# Encoder2.net
KiCad netlist of a schematic drawn in Altium Designer
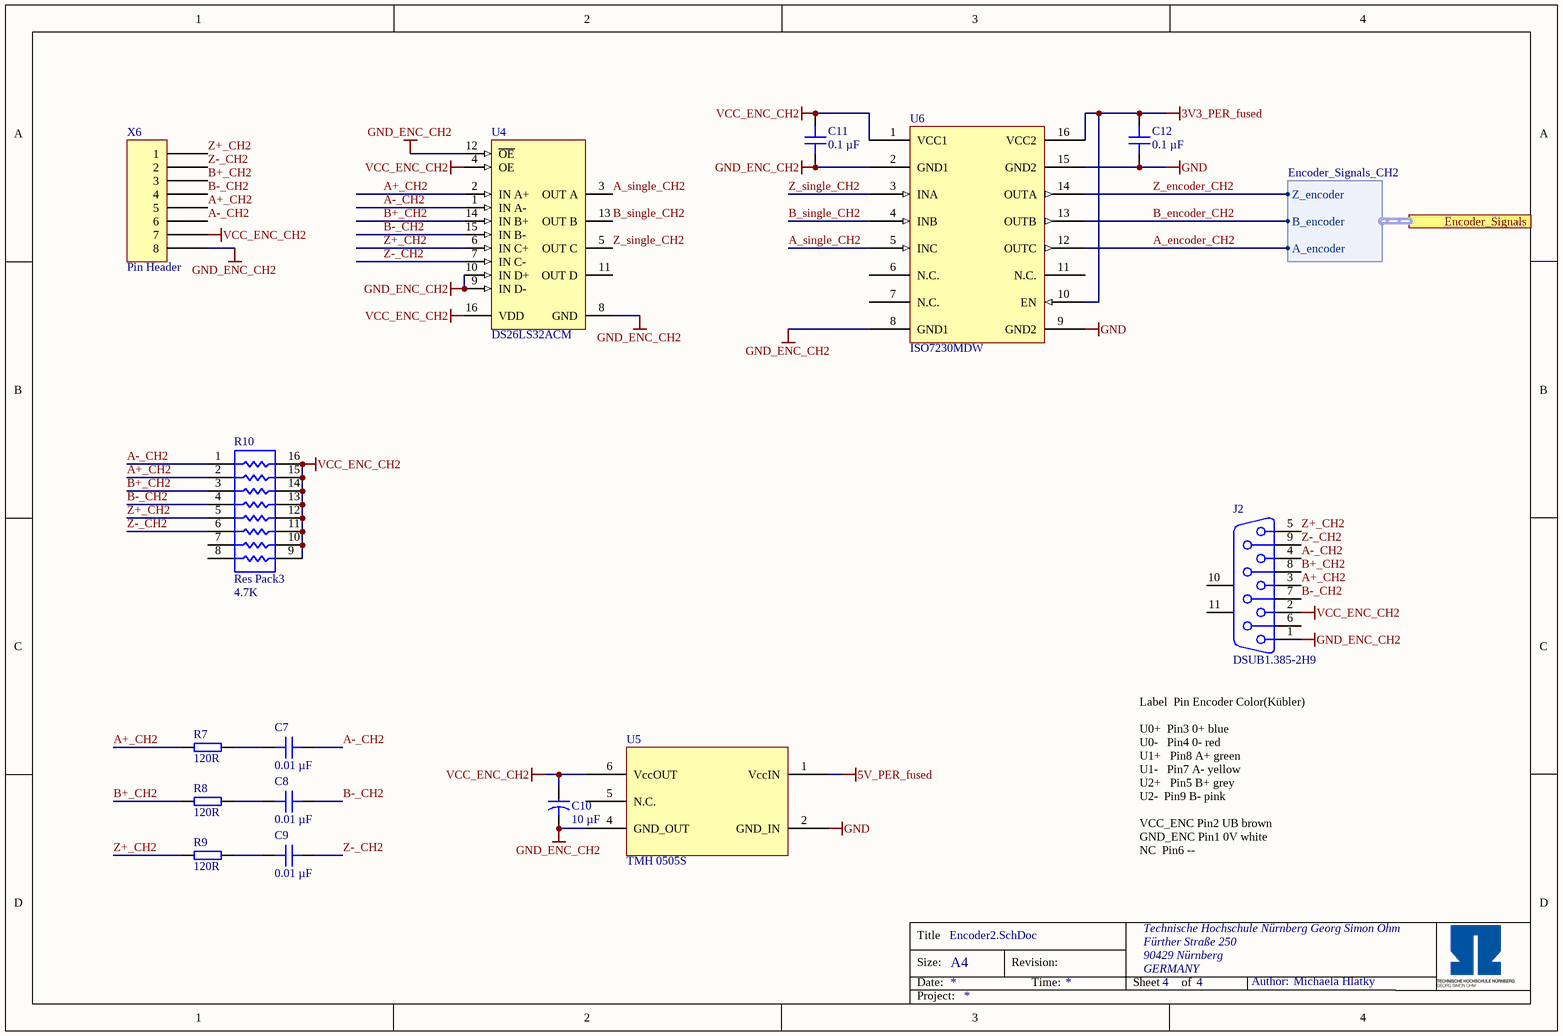
[diagram p0: Encoder2.SchDoc]

(export (version "E")
  (design (tool "Eeschema 10.0.6"))
  (components
    (comp (ref "C7")
      (value "0.01 µF")
      (footprint "C_0805")
      (description "Capacitor 0805, 100 VDC, 0.01 µF, X7R")
      (fields
        (field (name "MANUFACTURER PART NUMBER") "GRM21BR72A103KA01L")
        (field (name "MANUFACTURER") "Murata Electronics")
        (field (name "CREATED FROM") "MGremer")
      )
      (libsource (lib "user") (part "Capacitor"))
    )
    (comp (ref "C8")
      (value "0.01 µF")
      (footprint "C_0805")
      (description "Capacitor 0805, 100 VDC, 0.01 µF, X7R")
      (fields
        (field (name "MANUFACTURER PART NUMBER") "GRM21BR72A103KA01L")
        (field (name "MANUFACTURER") "Murata Electronics")
        (field (name "CREATED FROM") "MGremer")
      )
      (libsource (lib "user") (part "Capacitor"))
    )
    (comp (ref "C9")
      (value "0.01 µF")
      (footprint "C_0805")
      (description "Capacitor 0805, 100 VDC, 0.01 µF, X7R")
      (fields
        (field (name "MANUFACTURER PART NUMBER") "GRM21BR72A103KA01L")
        (field (name "MANUFACTURER") "Murata Electronics")
        (field (name "CREATED FROM") "MGremer")
      )
      (libsource (lib "user") (part "Capacitor"))
    )
    (comp (ref "C10")
      (value "10 µF")
      (footprint "CAPR5-4X5")
      (description "Capacitor; 2 Leads")
      (fields
        (field (name "MANUFACTURER PART NUMBER") "CAPR5-4X5")
        (field (name "PUBLISHER") "Altium Limited")
        (field (name "CREATED FROM") "MHlatky")
      )
      (libsource (lib "user") (part "Cap2"))
    )
    (comp (ref "C11")
      (value "0.1 µF")
      (footprint "C_0805")
      (description "Capacitor 0805, 50 VDC, 0.1 µF, X7R")
      (fields
        (field (name "MANUFACTURER PART NUMBER") "C0805C104J5RECTU")
        (field (name "MANUFACTURER") "KEMET")
        (field (name "CREATED FROM") "MGremer")
      )
      (libsource (lib "user") (part "Capacitor"))
    )
    (comp (ref "C12")
      (value "0.1 µF")
      (footprint "C_0805")
      (description "Capacitor 0805, 50 VDC, 0.1 µF, X7R")
      (fields
        (field (name "MANUFACTURER PART NUMBER") "C0805C104J5RECTU")
        (field (name "MANUFACTURER") "KEMET")
        (field (name "CREATED FROM") "MGremer")
      )
      (libsource (lib "user") (part "Capacitor"))
    )
    (comp (ref "J2")
      (value "DSUB1.385-2H9")
      (footprint "DSUB1.385-2H9")
      (description "Connector; D Subminiature; 9 Position; Right Angle; Pitch 1.385 mm")
      (fields
        (field (name "MANUFACTURER") "Altium")
        (field (name "PUBLISHER") "Altium Limited")
        (field (name "CREATED FROM") "MHlatky")
      )
      (libsource (lib "user") (part "D Connector 9"))
    )
    (comp (ref "R7")
      (value "120R")
      (footprint "RES 0603_1608")
      (description "SMD resistor E24 series")
      (fields
        (field (name "MANUFACTURER PART NUMBER") "RK73B1JTTD121J")
        (field (name "MANUFACTURER") "KOA Speer")
        (field (name "CREATED FROM") "MGremer")
      )
      (libsource (lib "user") (part "Resistor"))
    )
    (comp (ref "R8")
      (value "120R")
      (footprint "RES 0603_1608")
      (description "SMD resistor E24 series")
      (fields
        (field (name "MANUFACTURER PART NUMBER") "RK73B1JTTD121J")
        (field (name "MANUFACTURER") "KOA Speer")
        (field (name "CREATED FROM") "MGremer")
      )
      (libsource (lib "user") (part "Resistor"))
    )
    (comp (ref "R9")
      (value "120R")
      (footprint "RES 0603_1608")
      (description "SMD resistor E24 series")
      (fields
        (field (name "MANUFACTURER PART NUMBER") "RK73B1JTTD121J")
        (field (name "MANUFACTURER") "KOA Speer")
        (field (name "CREATED FROM") "MGremer")
      )
      (libsource (lib "user") (part "Resistor"))
    )
    (comp (ref "R10")
      (value "Res Pack3")
      (footprint "SO-16_N")
      (description "SOIC, 16-Leads, Body 9.9x3.9mm, Pitch 1.27mm, IPC Medium Density")
      (fields
        (field (name "ALTIUM_VALUE") "4.7K")
        (field (name "PUBLISHER") "Altium Limited")
        (field (name "CREATED FROM") "MHlatky")
      )
      (libsource (lib "user") (part "Res Pack3"))
    )
    (comp (ref "U4")
      (value "DS26LS32ACM")
      (footprint "M16A_M")
      (description "DS26LS32AC/DS26LS32C/DS26LS32M/DS26LS33M Quad Differential Line Receivers")
      (fields
        (field (name "MANUFACTURER") "Texas Instruments")
        (field (name "PUBLISHER") "Altium Limited")
        (field (name "CREATED FROM") "MHlatky")
      )
      (libsource (lib "user") (part "DS26LS32ACM"))
    )
    (comp (ref "U5")
      (value "TMH 0505S")
      (footprint "SIL-6(7)")
      (fields (field (name "MANUFACTURER") "Traco") (field (name "CREATED FROM") "MHlatky"))
      (libsource (lib "user") (part "TRACO TMH 0505S"))
    )
    (comp (ref "U6")
      (value "ISO7230MDW")
      (footprint "TI ISO7230 SOIC")
      (description "ISO723xx High-Speed, Triple-Channel Digital Isolators")
      (fields (field (name "MANUFACTURER") "Analog Devices") (field (name "CREATED FROM") "MHlatky"))
      (libsource (lib "user") (part "TI ISO7230"))
    )
    (comp (ref "X6")
      (value "Pin Header")
      (footprint "HDR1X8")
      (description "8 Pin")
      (fields (field (name "MANUFACTURER PART NUMBER") "HDR1X8") (field (name "CREATED FROM") "MHlatky"))
      (libsource (lib "user") (part "8 Pin"))
    )
  )
  (nets
    (net (code "2") (name "/A+_CH2") (class "Default")
      (node (ref "J2") (pin "3") (pinfunction "3_3") (pintype "passive"))
      (node (ref "R10") (pin "2") (pinfunction "2_2") (pintype "passive"))
      (node (ref "R7") (pin "1") (pinfunction "1_1") (pintype "passive"))
      (node (ref "U4") (pin "2") (pinfunction "IN_A+_2") (pintype "input"))
      (node (ref "X6") (pin "5") (pinfunction "5_5") (pintype "passive"))
    )
    (net (code "3") (name "/A-_CH2") (class "Default")
      (node (ref "C7") (pin "2") (pinfunction "2_2") (pintype "passive"))
      (node (ref "J2") (pin "4") (pinfunction "4_4") (pintype "passive"))
      (node (ref "R10") (pin "1") (pinfunction "1_1") (pintype "passive"))
      (node (ref "U4") (pin "1") (pinfunction "IN_A-_1") (pintype "input"))
      (node (ref "X6") (pin "6") (pinfunction "6_6") (pintype "passive"))
    )
    (net (code "4") (name "/A_encoder_CH2") (class "Default")
      (node (ref "U6") (pin "12") (pinfunction "OUTC_12") (pintype "output"))
    )
    (net (code "5") (name "/A_single_CH2") (class "Default")
      (node (ref "U4") (pin "3") (pinfunction "OUT_A_3") (pintype "tri_state"))
      (node (ref "U6") (pin "5") (pinfunction "INC_5") (pintype "input"))
    )
    (net (code "6") (name "/B+_CH2") (class "Default")
      (node (ref "J2") (pin "8") (pinfunction "8_8") (pintype "passive"))
      (node (ref "R10") (pin "3") (pinfunction "3_3") (pintype "passive"))
      (node (ref "R8") (pin "1") (pinfunction "1_1") (pintype "passive"))
      (node (ref "U4") (pin "14") (pinfunction "IN_B+_14") (pintype "input"))
      (node (ref "X6") (pin "3") (pinfunction "3_3") (pintype "passive"))
    )
    (net (code "7") (name "/B-_CH2") (class "Default")
      (node (ref "C8") (pin "2") (pinfunction "2_2") (pintype "passive"))
      (node (ref "J2") (pin "7") (pinfunction "7_7") (pintype "passive"))
      (node (ref "R10") (pin "4") (pinfunction "4_4") (pintype "passive"))
      (node (ref "U4") (pin "15") (pinfunction "IN_B-_15") (pintype "input"))
      (node (ref "X6") (pin "4") (pinfunction "4_4") (pintype "passive"))
    )
    (net (code "8") (name "/B_encoder_CH2") (class "Default")
      (node (ref "U6") (pin "13") (pinfunction "OUTB_13") (pintype "output"))
    )
    (net (code "9") (name "/B_single_CH2") (class "Default")
      (node (ref "U4") (pin "13") (pinfunction "OUT_B_13") (pintype "tri_state"))
      (node (ref "U6") (pin "4") (pinfunction "INB_4") (pintype "input"))
    )
    (net (code "10") (name "/Z+_CH2") (class "Default")
      (node (ref "J2") (pin "5") (pinfunction "5_5") (pintype "passive"))
      (node (ref "R10") (pin "5") (pinfunction "5_5") (pintype "passive"))
      (node (ref "R9") (pin "1") (pinfunction "1_1") (pintype "passive"))
      (node (ref "U4") (pin "6") (pinfunction "IN_C+_6") (pintype "input"))
      (node (ref "X6") (pin "1") (pinfunction "1_1") (pintype "passive"))
    )
    (net (code "11") (name "/Z-_CH2") (class "Default")
      (node (ref "C9") (pin "2") (pinfunction "2_2") (pintype "passive"))
      (node (ref "J2") (pin "9") (pinfunction "9_9") (pintype "passive"))
      (node (ref "R10") (pin "6") (pinfunction "6_6") (pintype "passive"))
      (node (ref "U4") (pin "7") (pinfunction "IN_C-_7") (pintype "input"))
      (node (ref "X6") (pin "2") (pinfunction "2_2") (pintype "passive"))
    )
    (net (code "12") (name "/Z_encoder_CH2") (class "Default")
      (node (ref "U6") (pin "14") (pinfunction "OUTA_14") (pintype "output"))
    )
    (net (code "13") (name "/Z_single_CH2") (class "Default")
      (node (ref "U4") (pin "5") (pinfunction "OUT_C_5") (pintype "tri_state"))
      (node (ref "U6") (pin "3") (pinfunction "INA_3") (pintype "input"))
    )
    (net (code "15") (name "3V3_PER_fused") (class "Default")
      (node (ref "C12") (pin "2") (pinfunction "2_2") (pintype "passive"))
      (node (ref "U6") (pin "10") (pinfunction "EN_10") (pintype "input"))
      (node (ref "U6") (pin "16") (pinfunction "VCC2_16") (pintype "passive"))
    )
    (net (code "16") (name "5V_PER_fused") (class "Default")
      (node (ref "U5") (pin "1") (pinfunction "VccIN_1") (pintype "passive"))
    )
    (net (code "17") (name "GND") (class "Default")
      (node (ref "C12") (pin "1") (pinfunction "1_1") (pintype "passive"))
      (node (ref "U5") (pin "2") (pinfunction "GND_IN_2") (pintype "passive"))
      (node (ref "U6") (pin "15") (pinfunction "GND2_15") (pintype "passive"))
      (node (ref "U6") (pin "9") (pinfunction "GND2_9") (pintype "passive"))
    )
    (net (code "18") (name "GND_ENC_CH2") (class "Default")
      (node (ref "C10") (pin "2") (pinfunction "2_2") (pintype "passive"))
      (node (ref "C11") (pin "1") (pinfunction "1_1") (pintype "passive"))
      (node (ref "J2") (pin "1") (pinfunction "1_1") (pintype "passive"))
      (node (ref "U4") (pin "10") (pinfunction "IN_D+_10") (pintype "input"))
      (node (ref "U4") (pin "12") (pinfunction "~{OE}_12") (pintype "input"))
      (node (ref "U4") (pin "8") (pinfunction "GND_8") (pintype "power_in"))
      (node (ref "U4") (pin "9") (pinfunction "IN_D-_9") (pintype "input"))
      (node (ref "U5") (pin "4") (pinfunction "GND_OUT_4") (pintype "passive"))
      (node (ref "U6") (pin "2") (pinfunction "GND1_2") (pintype "passive"))
      (node (ref "U6") (pin "8") (pinfunction "GND1_8") (pintype "passive"))
      (node (ref "X6") (pin "8") (pinfunction "8_8") (pintype "passive"))
    )
    (net (code "19") (name "Net-(C7-Pad1)") (class "Default")
      (node (ref "C7") (pin "1") (pinfunction "1_1") (pintype "passive"))
      (node (ref "R7") (pin "2") (pinfunction "2_2") (pintype "passive"))
    )
    (net (code "20") (name "Net-(C8-Pad1)") (class "Default")
      (node (ref "C8") (pin "1") (pinfunction "1_1") (pintype "passive"))
      (node (ref "R8") (pin "2") (pinfunction "2_2") (pintype "passive"))
    )
    (net (code "21") (name "Net-(C9-Pad1)") (class "Default")
      (node (ref "C9") (pin "1") (pinfunction "1_1") (pintype "passive"))
      (node (ref "R9") (pin "2") (pinfunction "2_2") (pintype "passive"))
    )
    (net (code "22") (name "VCC_ENC_CH2") (class "Default")
      (node (ref "C10") (pin "1") (pinfunction "1_1") (pintype "passive"))
      (node (ref "C11") (pin "2") (pinfunction "2_2") (pintype "passive"))
      (node (ref "J2") (pin "2") (pinfunction "2_2") (pintype "passive"))
      (node (ref "R10") (pin "10") (pinfunction "10_10") (pintype "passive"))
      (node (ref "R10") (pin "11") (pinfunction "11_11") (pintype "passive"))
      (node (ref "R10") (pin "12") (pinfunction "12_12") (pintype "passive"))
      (node (ref "R10") (pin "13") (pinfunction "13_13") (pintype "passive"))
      (node (ref "R10") (pin "14") (pinfunction "14_14") (pintype "passive"))
      (node (ref "R10") (pin "15") (pinfunction "15_15") (pintype "passive"))
      (node (ref "R10") (pin "16") (pinfunction "16_16") (pintype "passive"))
      (node (ref "R10") (pin "9") (pinfunction "9_9") (pintype "passive"))
      (node (ref "U4") (pin "16") (pinfunction "VDD_16") (pintype "power_in"))
      (node (ref "U4") (pin "4") (pinfunction "OE_4") (pintype "input"))
      (node (ref "U5") (pin "6") (pinfunction "VccOUT_6") (pintype "passive"))
      (node (ref "U6") (pin "1") (pinfunction "VCC1_1") (pintype "passive"))
      (node (ref "X6") (pin "7") (pinfunction "7_7") (pintype "passive"))
    )
    (net (code "23") (name "unconnected-(J2-MH1-Pad10)") (class "Default")
      (node (ref "J2") (pin "10") (pinfunction "MH1_10") (pintype "passive"))
    )
    (net (code "24") (name "unconnected-(J2-MH2-Pad11)") (class "Default")
      (node (ref "J2") (pin "11") (pinfunction "MH2_11") (pintype "passive"))
    )
    (net (code "25") (name "unconnected-(J2-Pad6)") (class "Default")
      (node (ref "J2") (pin "6") (pinfunction "6_6") (pintype "passive"))
    )
    (net (code "26") (name "unconnected-(R10-Pad7)") (class "Default")
      (node (ref "R10") (pin "7") (pinfunction "7_7") (pintype "passive"))
    )
    (net (code "27") (name "unconnected-(R10-Pad8)") (class "Default")
      (node (ref "R10") (pin "8") (pinfunction "8_8") (pintype "passive"))
    )
    (net (code "28") (name "unconnected-(U4-OUT_D-Pad11)") (class "Default")
      (node (ref "U4") (pin "11") (pinfunction "OUT_D_11") (pintype "tri_state"))
    )
    (net (code "29") (name "unconnected-(U5-N.C.-Pad5)") (class "Default")
      (node (ref "U5") (pin "5") (pinfunction "N.C._5") (pintype "passive"))
    )
    (net (code "30") (name "unconnected-(U6-N.C.-Pad6)") (class "Default")
      (node (ref "U6") (pin "6") (pinfunction "N.C._6") (pintype "passive"))
    )
    (net (code "31") (name "unconnected-(U6-N.C.-Pad7)") (class "Default")
      (node (ref "U6") (pin "7") (pinfunction "N.C._7") (pintype "passive"))
    )
    (net (code "32") (name "unconnected-(U6-N.C.-Pad11)") (class "Default")
      (node (ref "U6") (pin "11") (pinfunction "N.C._11") (pintype "passive"))
    )
  )
)
